# power.net
KiCad netlist of a schematic drawn in Altium Designer
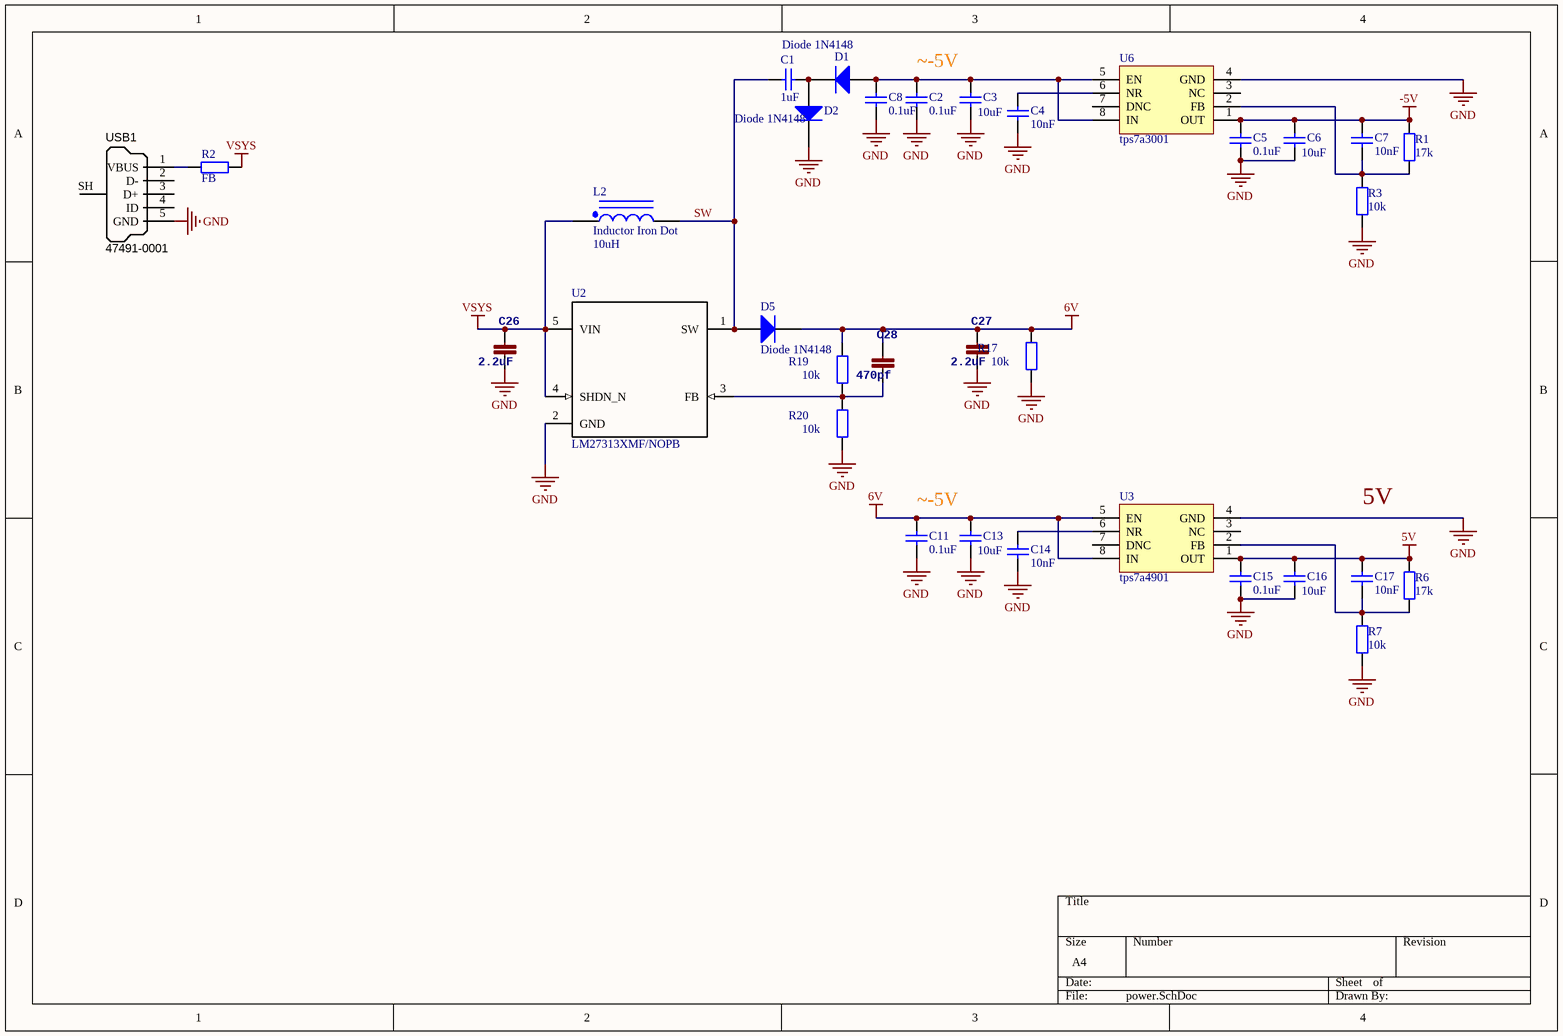
[diagram p0: power.SchDoc]

(export (version "E")
  (design (tool "Eeschema 10.0.6"))
  (components
    (comp (ref "C1")
      (value "1uF")
      (footprint "0603")
      (description "Capacitor")
      (fields (field (name "PUBLISHER") "Altium Limited"))
      (libsource (lib "RTC6705") (part "Cap"))
    )
    (comp (ref "C2")
      (value "0.1uF")
      (footprint "0603")
      (description "Capacitor")
      (fields (field (name "PUBLISHER") "Altium Limited"))
      (libsource (lib "RTC6705") (part "Cap"))
    )
    (comp (ref "C3")
      (value "10uF")
      (footprint "0805")
      (description "Capacitor")
      (fields (field (name "PUBLISHER") "Altium Limited"))
      (libsource (lib "RTC6705") (part "Cap"))
    )
    (comp (ref "C4")
      (value "10nF")
      (footprint "0402")
      (description "Capacitor")
      (fields (field (name "PUBLISHER") "Altium Limited"))
      (libsource (lib "RTC6705") (part "Cap"))
    )
    (comp (ref "C5")
      (value "0.1uF")
      (footprint "0603")
      (description "Capacitor")
      (fields (field (name "PUBLISHER") "Altium Limited"))
      (libsource (lib "RTC6705") (part "Cap"))
    )
    (comp (ref "C6")
      (value "10uF")
      (footprint "0805")
      (description "Capacitor")
      (fields (field (name "PUBLISHER") "Altium Limited"))
      (libsource (lib "RTC6705") (part "Cap"))
    )
    (comp (ref "C7")
      (value "10nF")
      (footprint "0402")
      (description "Capacitor")
      (fields (field (name "PUBLISHER") "Altium Limited"))
      (libsource (lib "RTC6705") (part "Cap"))
    )
    (comp (ref "C8")
      (value "0.1uF")
      (footprint "0603")
      (description "Capacitor")
      (fields (field (name "PUBLISHER") "Altium Limited"))
      (libsource (lib "RTC6705") (part "Cap"))
    )
    (comp (ref "C11")
      (value "0.1uF")
      (footprint "0603")
      (description "Capacitor")
      (fields (field (name "PUBLISHER") "Altium Limited"))
      (libsource (lib "RTC6705") (part "Cap"))
    )
    (comp (ref "C13")
      (value "10uF")
      (footprint "0805")
      (description "Capacitor")
      (fields (field (name "PUBLISHER") "Altium Limited"))
      (libsource (lib "RTC6705") (part "Cap"))
    )
    (comp (ref "C14")
      (value "10nF")
      (footprint "0402")
      (description "Capacitor")
      (fields (field (name "PUBLISHER") "Altium Limited"))
      (libsource (lib "RTC6705") (part "Cap"))
    )
    (comp (ref "C15")
      (value "0.1uF")
      (footprint "0603")
      (description "Capacitor")
      (fields (field (name "PUBLISHER") "Altium Limited"))
      (libsource (lib "RTC6705") (part "Cap"))
    )
    (comp (ref "C16")
      (value "10uF")
      (footprint "0805")
      (description "Capacitor")
      (fields (field (name "PUBLISHER") "Altium Limited"))
      (libsource (lib "RTC6705") (part "Cap"))
    )
    (comp (ref "C17")
      (value "10nF")
      (footprint "0402")
      (description "Capacitor")
      (fields (field (name "PUBLISHER") "Altium Limited"))
      (libsource (lib "RTC6705") (part "Cap"))
    )
    (comp (ref "C26")
      (value "2.2uF")
      (footprint "0805")
      (description "<b>Capacitor</b>\nStandard 0603 ceramic capacitor, and 0.1\" leaded capacitor.")
      (fields (field (name "PARTNO") "CC0402ZRY5V7BB104"))
      (libsource (lib "pixhawk2") (part "CAP0402-CAP"))
    )
    (comp (ref "C27")
      (value "2.2uF")
      (footprint "0805")
      (description "<b>Capacitor</b>\nStandard 0603 ceramic capacitor, and 0.1\" leaded capacitor.")
      (fields (field (name "PARTNO") "CC0402ZRY5V7BB104"))
      (libsource (lib "pixhawk2") (part "CAP0402-CAP"))
    )
    (comp (ref "C28")
      (value "470pf")
      (footprint "0402")
      (description "<b>Capacitor</b>\nStandard 0603 ceramic capacitor, and 0.1\" leaded capacitor.")
      (fields (field (name "PARTNO") "CC0402ZRY5V7BB104"))
      (libsource (lib "pixhawk2") (part "CAP0402-CAP"))
    )
    (comp (ref "D1")
      (value "Diode 1N4148")
      (footprint "LC-SOD-323")
      (description "High Conductance Fast Diode")
      (fields (field (name "PUBLISHER") "Altium Limited"))
      (libsource (lib "Miscellaneous Devices") (part "Diode 1N4148"))
    )
    (comp (ref "D2")
      (value "Diode 1N4148")
      (footprint "LC-SOD-323")
      (description "High Conductance Fast Diode")
      (fields (field (name "PUBLISHER") "Altium Limited"))
      (libsource (lib "Miscellaneous Devices") (part "Diode 1N4148"))
    )
    (comp (ref "D5")
      (value "Diode 1N4148")
      (footprint "LC-SOD-323")
      (description "High Conductance Fast Diode")
      (fields (field (name "PUBLISHER") "Altium Limited"))
      (libsource (lib "Miscellaneous Devices") (part "Diode 1N4148"))
    )
    (comp (ref "L2")
      (value "Inductor Iron Dot")
      (footprint "L4015")
      (description "Magnetic-Core Inductor with Winding Polarity Marking")
      (fields (field (name "ALTIUM_VALUE") "10uH") (field (name "PUBLISHER") "Altium Limited"))
      (libsource (lib "Miscellaneous Devices") (part "Inductor Iron Dot"))
    )
    (comp (ref "R1")
      (value "17k")
      (footprint "0402")
      (description "Resistor")
      (fields (field (name "PUBLISHER") "Altium Limited"))
      (libsource (lib "RTC6705") (part "Res2"))
    )
    (comp (ref "R2")
      (value "FB")
      (footprint "0603")
      (description "Resistor")
      (fields (field (name "PUBLISHER") "Altium Limited"))
      (libsource (lib "") (part "Res2_1"))
    )
    (comp (ref "R3")
      (value "10k")
      (footprint "0402")
      (description "Resistor")
      (fields (field (name "PUBLISHER") "Altium Limited"))
      (libsource (lib "RTC6705") (part "Res2"))
    )
    (comp (ref "R6")
      (value "17k")
      (footprint "0402")
      (description "Resistor")
      (fields (field (name "PUBLISHER") "Altium Limited"))
      (libsource (lib "RTC6705") (part "Res2"))
    )
    (comp (ref "R7")
      (value "10k")
      (footprint "0402")
      (description "Resistor")
      (fields (field (name "PUBLISHER") "Altium Limited"))
      (libsource (lib "RTC6705") (part "Res2"))
    )
    (comp (ref "R17")
      (value "10k")
      (footprint "0402")
      (description "Resistor")
      (fields (field (name "PUBLISHER") "Altium Limited"))
      (libsource (lib "Miscellaneous Devices") (part "Res2"))
    )
    (comp (ref "R19")
      (value "10k")
      (footprint "0402")
      (description "Resistor")
      (fields (field (name "PUBLISHER") "Altium Limited"))
      (libsource (lib "Miscellaneous Devices") (part "Res2"))
    )
    (comp (ref "R20")
      (value "10k")
      (footprint "0402")
      (description "Resistor")
      (fields (field (name "PUBLISHER") "Altium Limited"))
      (libsource (lib "Miscellaneous Devices") (part "Res2"))
    )
    (comp (ref "U2")
      (value "LM27313XMF/NOPB")
      (footprint "SOT23-5")
      (description "Imported")
      (fields (field (name "MANUFACTURER") "Texas Instruments"))
      (libsource (lib "complements") (part "LM27313XMF/NOPB"))
    )
    (comp (ref "U3")
      (value "tps7a4901")
      (footprint "MSOP8/VSSOP8")
      (libsource (lib "F4SDR") (part "tps7a3001"))
    )
    (comp (ref "U6")
      (value "tps7a3001")
      (footprint "MSOP8/VSSOP8")
      (libsource (lib "F4SDR") (part "tps7a3001"))
    )
    (comp (ref "USB1")
      (value "USB Micro Type B")
      (footprint "MICRO-YZX")
      (description "Connector SMD USB Micro Type B middle mount")
      (fields (field (name "MANUFACTURER PART NUMBER 1") "47491-0001"))
      (libsource (lib "PBL - Connectors") (part "USB_Micro_TypeB"))
    )
  )
  (nets
    (net (code "1") (name "-5V") (class "Default")
      (node (ref "C5") (pin "1") (pinfunction "1_1") (pintype "passive"))
      (node (ref "C6") (pin "2") (pinfunction "2_2") (pintype "passive"))
      (node (ref "C7") (pin "1") (pinfunction "1_1") (pintype "passive"))
      (node (ref "R1") (pin "2") (pinfunction "2_2") (pintype "passive"))
      (node (ref "U6") (pin "1") (pinfunction "OUT_1") (pintype "passive"))
    )
    (net (code "2") (name "/SW") (class "Default")
      (node (ref "C1") (pin "2") (pinfunction "2_2") (pintype "passive"))
      (node (ref "D5") (pin "1") (pinfunction "A_1") (pintype "passive"))
      (node (ref "L2") (pin "2") (pinfunction "2_2") (pintype "passive"))
      (node (ref "U2") (pin "1") (pinfunction "SW_1") (pintype "power_in"))
    )
    (net (code "3") (name "5V") (class "Default")
      (node (ref "C15") (pin "1") (pinfunction "1_1") (pintype "passive"))
      (node (ref "C16") (pin "2") (pinfunction "2_2") (pintype "passive"))
      (node (ref "C17") (pin "1") (pinfunction "1_1") (pintype "passive"))
      (node (ref "R6") (pin "2") (pinfunction "2_2") (pintype "passive"))
      (node (ref "U3") (pin "1") (pinfunction "OUT_1") (pintype "passive"))
    )
    (net (code "4") (name "6V") (class "Default")
      (node (ref "C11") (pin "1") (pinfunction "1_1") (pintype "passive"))
      (node (ref "C13") (pin "2") (pinfunction "2_2") (pintype "passive"))
      (node (ref "C27") (pin "2") (pinfunction "2_2") (pintype "passive"))
      (node (ref "C28") (pin "2") (pinfunction "2_2") (pintype "passive"))
      (node (ref "D5") (pin "2") (pinfunction "K_2") (pintype "passive"))
      (node (ref "R17") (pin "2") (pinfunction "2_2") (pintype "passive"))
      (node (ref "R19") (pin "2") (pinfunction "2_2") (pintype "passive"))
      (node (ref "U3") (pin "5") (pinfunction "EN_5") (pintype "passive"))
      (node (ref "U3") (pin "8") (pinfunction "IN_8") (pintype "passive"))
    )
    (net (code "5") (name "GND") (class "Default")
      (node (ref "C11") (pin "2") (pinfunction "2_2") (pintype "passive"))
      (node (ref "C13") (pin "1") (pinfunction "1_1") (pintype "passive"))
      (node (ref "C14") (pin "2") (pinfunction "2_2") (pintype "passive"))
      (node (ref "C15") (pin "2") (pinfunction "2_2") (pintype "passive"))
      (node (ref "C16") (pin "1") (pinfunction "1_1") (pintype "passive"))
      (node (ref "C2") (pin "2") (pinfunction "2_2") (pintype "passive"))
      (node (ref "C26") (pin "1") (pinfunction "1_1") (pintype "passive"))
      (node (ref "C27") (pin "1") (pinfunction "1_1") (pintype "passive"))
      (node (ref "C3") (pin "1") (pinfunction "1_1") (pintype "passive"))
      (node (ref "C4") (pin "2") (pinfunction "2_2") (pintype "passive"))
      (node (ref "C5") (pin "2") (pinfunction "2_2") (pintype "passive"))
      (node (ref "C6") (pin "1") (pinfunction "1_1") (pintype "passive"))
      (node (ref "C8") (pin "2") (pinfunction "2_2") (pintype "passive"))
      (node (ref "D2") (pin "2") (pinfunction "K_2") (pintype "passive"))
      (node (ref "R17") (pin "1") (pinfunction "1_1") (pintype "passive"))
      (node (ref "R20") (pin "1") (pinfunction "1_1") (pintype "passive"))
      (node (ref "R3") (pin "1") (pinfunction "1_1") (pintype "passive"))
      (node (ref "R7") (pin "1") (pinfunction "1_1") (pintype "passive"))
      (node (ref "U2") (pin "2") (pinfunction "GND_2") (pintype "power_in"))
      (node (ref "U3") (pin "4") (pinfunction "GND_4") (pintype "passive"))
      (node (ref "U6") (pin "4") (pinfunction "GND_4") (pintype "passive"))
      (node (ref "USB1") (pin "5") (pinfunction "GND_5") (pintype "passive"))
    )
    (net (code "6") (name "Net-(D1-A)") (class "Default")
      (node (ref "C2") (pin "1") (pinfunction "1_1") (pintype "passive"))
      (node (ref "C3") (pin "2") (pinfunction "2_2") (pintype "passive"))
      (node (ref "C8") (pin "1") (pinfunction "1_1") (pintype "passive"))
      (node (ref "D1") (pin "1") (pinfunction "A_1") (pintype "passive"))
      (node (ref "U6") (pin "5") (pinfunction "EN_5") (pintype "passive"))
      (node (ref "U6") (pin "8") (pinfunction "IN_8") (pintype "passive"))
    )
    (net (code "7") (name "Net-(D1-K)") (class "Default")
      (node (ref "C1") (pin "1") (pinfunction "1_1") (pintype "passive"))
      (node (ref "D1") (pin "2") (pinfunction "K_2") (pintype "passive"))
      (node (ref "D2") (pin "1") (pinfunction "A_1") (pintype "passive"))
    )
    (net (code "8") (name "Net-(U2-FB)") (class "Default")
      (node (ref "C28") (pin "1") (pinfunction "1_1") (pintype "passive"))
      (node (ref "R19") (pin "1") (pinfunction "1_1") (pintype "passive"))
      (node (ref "R20") (pin "2") (pinfunction "2_2") (pintype "passive"))
      (node (ref "U2") (pin "3") (pinfunction "FB_3") (pintype "input"))
    )
    (net (code "9") (name "Net-(U3-FB)") (class "Default")
      (node (ref "C17") (pin "2") (pinfunction "2_2") (pintype "passive"))
      (node (ref "R6") (pin "1") (pinfunction "1_1") (pintype "passive"))
      (node (ref "R7") (pin "2") (pinfunction "2_2") (pintype "passive"))
      (node (ref "U3") (pin "2") (pinfunction "FB_2") (pintype "passive"))
    )
    (net (code "10") (name "Net-(U3-NR)") (class "Default")
      (node (ref "C14") (pin "1") (pinfunction "1_1") (pintype "passive"))
      (node (ref "U3") (pin "6") (pinfunction "NR_6") (pintype "passive"))
    )
    (net (code "11") (name "Net-(U6-FB)") (class "Default")
      (node (ref "C7") (pin "2") (pinfunction "2_2") (pintype "passive"))
      (node (ref "R1") (pin "1") (pinfunction "1_1") (pintype "passive"))
      (node (ref "R3") (pin "2") (pinfunction "2_2") (pintype "passive"))
      (node (ref "U6") (pin "2") (pinfunction "FB_2") (pintype "passive"))
    )
    (net (code "12") (name "Net-(U6-NR)") (class "Default")
      (node (ref "C4") (pin "1") (pinfunction "1_1") (pintype "passive"))
      (node (ref "U6") (pin "6") (pinfunction "NR_6") (pintype "passive"))
    )
    (net (code "13") (name "Net-(USB1-VBUS)") (class "Default")
      (node (ref "R2") (pin "1") (pinfunction "1_1") (pintype "passive"))
      (node (ref "USB1") (pin "1") (pinfunction "VBUS_1") (pintype "passive"))
    )
    (net (code "14") (name "VSYS") (class "Default")
      (node (ref "C26") (pin "2") (pinfunction "2_2") (pintype "passive"))
      (node (ref "L2") (pin "1") (pinfunction "1_1") (pintype "passive"))
      (node (ref "R2") (pin "2") (pinfunction "2_2") (pintype "passive"))
      (node (ref "U2") (pin "4") (pinfunction "SHDN_N_4") (pintype "input"))
      (node (ref "U2") (pin "5") (pinfunction "VIN_5") (pintype "power_in"))
    )
    (net (code "15") (name "unconnected-(U3-DNC-Pad7)") (class "Default")
      (node (ref "U3") (pin "7") (pinfunction "DNC_7") (pintype "passive"))
    )
    (net (code "16") (name "unconnected-(U3-NC-Pad3)") (class "Default")
      (node (ref "U3") (pin "3") (pinfunction "NC_3") (pintype "passive"))
    )
    (net (code "17") (name "unconnected-(U6-DNC-Pad7)") (class "Default")
      (node (ref "U6") (pin "7") (pinfunction "DNC_7") (pintype "passive"))
    )
    (net (code "18") (name "unconnected-(U6-NC-Pad3)") (class "Default")
      (node (ref "U6") (pin "3") (pinfunction "NC_3") (pintype "passive"))
    )
    (net (code "19") (name "unconnected-(USB1-D+-Pad3)") (class "Default")
      (node (ref "USB1") (pin "3") (pinfunction "D+_3") (pintype "passive"))
    )
    (net (code "20") (name "unconnected-(USB1-D--Pad2)") (class "Default")
      (node (ref "USB1") (pin "2") (pinfunction "D-_2") (pintype "passive"))
    )
    (net (code "21") (name "unconnected-(USB1-ID-Pad4)") (class "Default")
      (node (ref "USB1") (pin "4") (pinfunction "ID_4") (pintype "passive"))
    )
    (net (code "22") (name "unconnected-(USB1-Shell-PadSH)") (class "Default")
      (node (ref "USB1") (pin "SH") (pinfunction "Shell_SH") (pintype "passive"))
    )
  )
)
